# FLC100_shield_v2_0.net
KiCad netlist of a schematic drawn in EAGLE
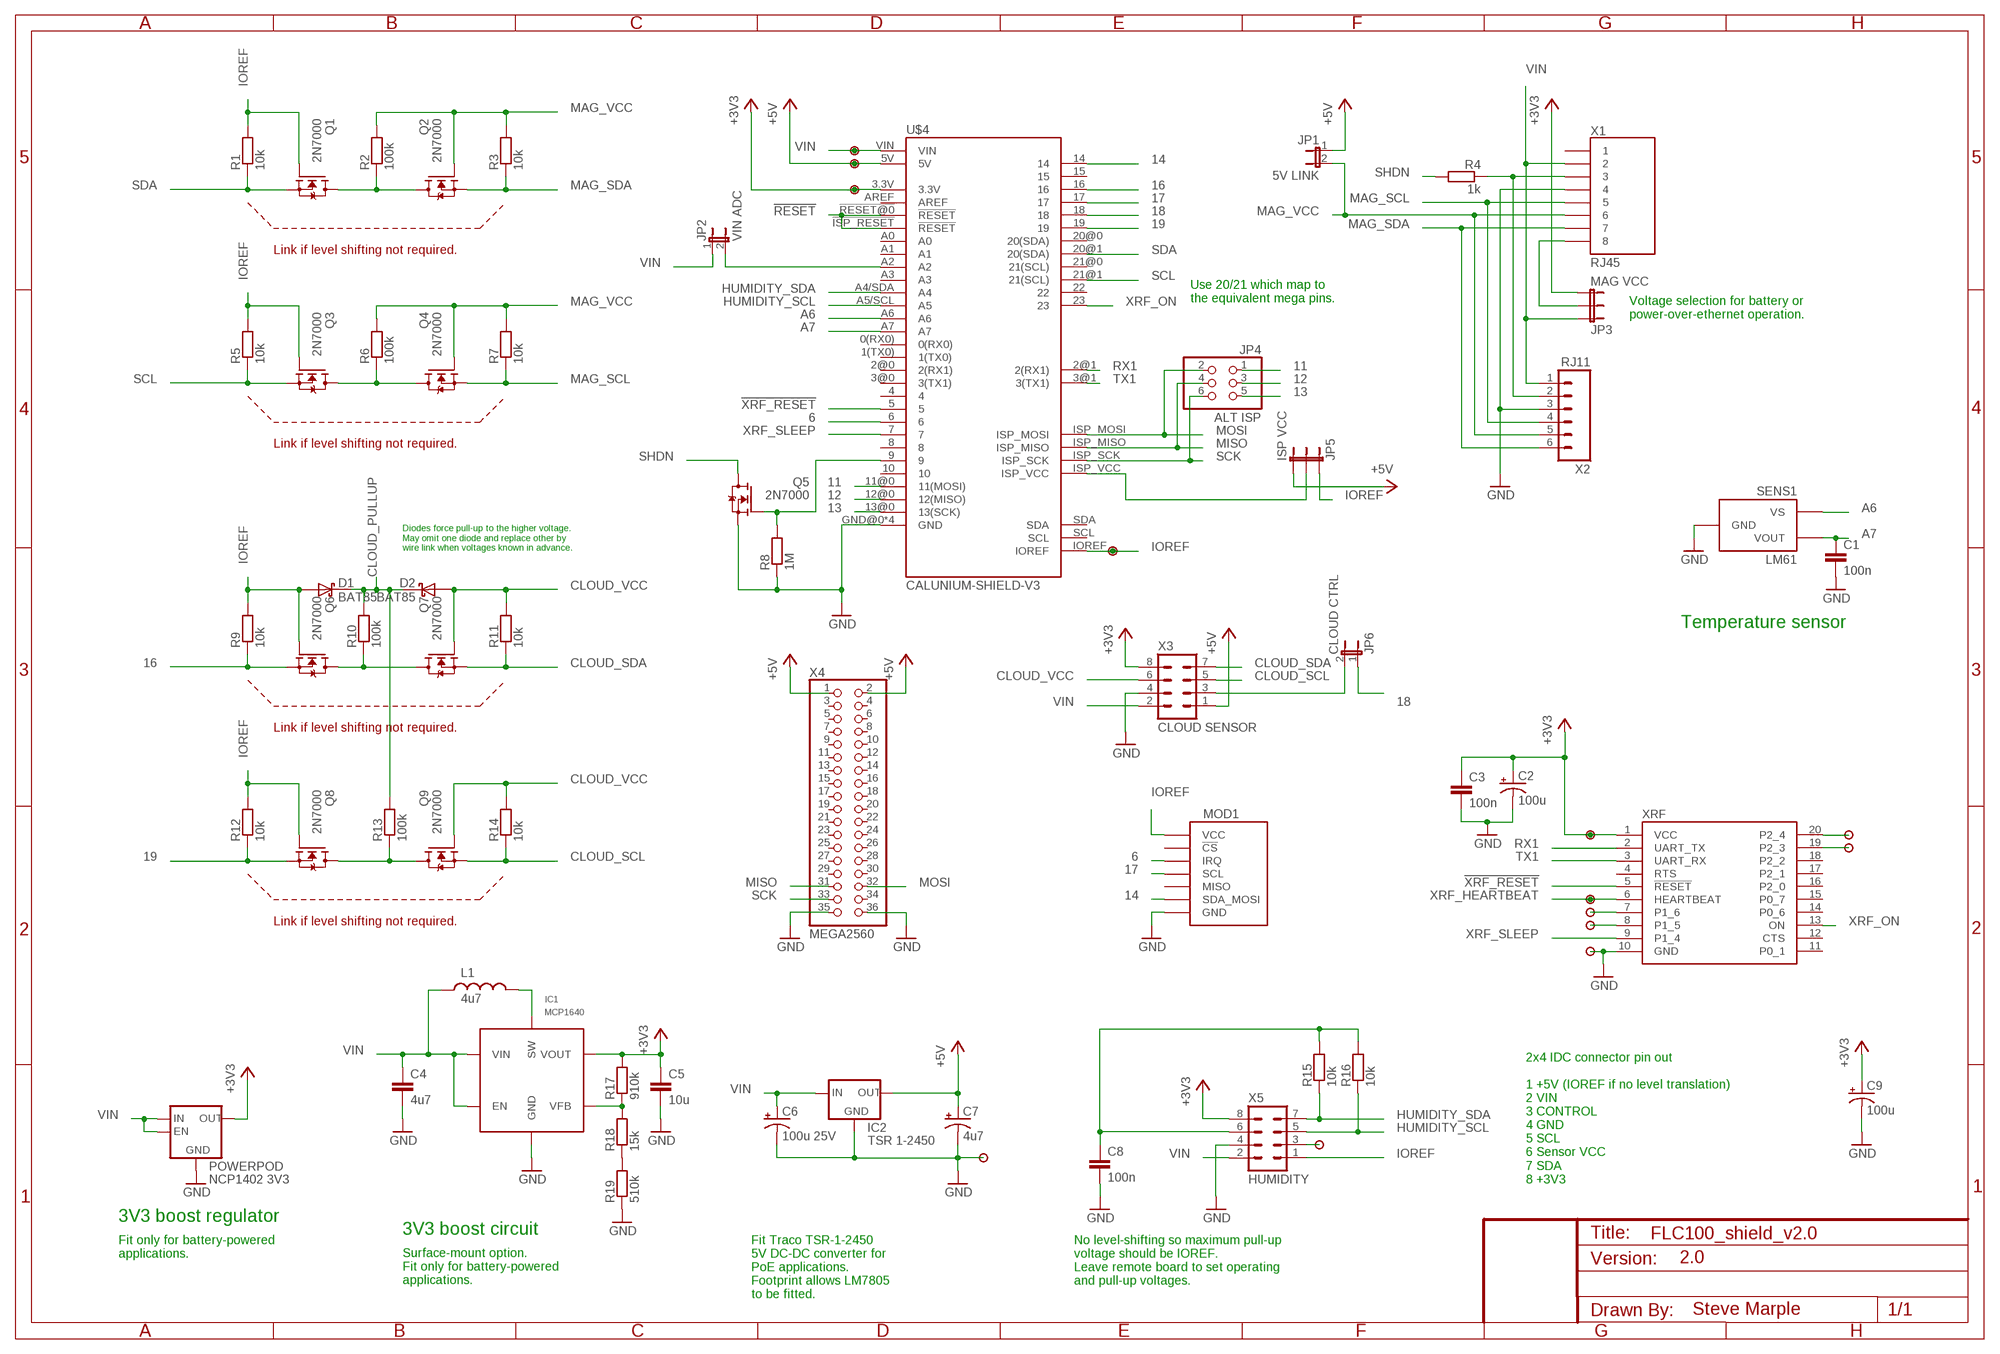
[diagram p0: schematic, sheet 1]

(export (version "E")
  (design (tool "Eeschema 10.0.6"))
  (components
    (comp (ref "C1")
      (value "100n")
      (footprint "eagle-import:CAP-PTH-SMALL")
      (libsource (lib "eagle-import") (part "CAPPTH"))
    )
    (comp (ref "C2")
      (value "100u")
      (footprint "eagle-import:CPOL-RADIAL-10UF-25V")
      (libsource (lib "eagle-import") (part "CAP_POLPTH2"))
    )
    (comp (ref "C3")
      (value "100n")
      (footprint "eagle-import:CAP-PTH-SMALL")
      (libsource (lib "eagle-import") (part "CAPPTH"))
    )
    (comp (ref "C4")
      (value "4u7")
      (footprint "eagle-import:1206-HAND")
      (libsource (lib "eagle-import") (part "C-EU1206-HAND"))
    )
    (comp (ref "C5")
      (value "10u")
      (footprint "eagle-import:1206-HAND")
      (libsource (lib "eagle-import") (part "C-EU1206-HAND"))
    )
    (comp (ref "C6")
      (value "100u 25V")
      (footprint "eagle-import:CPOL-RADIAL-100UF-25V-150MIL")
      (libsource (lib "eagle-import") (part "CAP_POL"))
    )
    (comp (ref "C7")
      (value "4u7")
      (footprint "eagle-import:CPOL-RADIAL-10UF-25V")
      (libsource (lib "eagle-import") (part "CAP_POLPTH2"))
    )
    (comp (ref "C8")
      (value "100n")
      (footprint "eagle-import:CAP-PTH-SMALL")
      (libsource (lib "eagle-import") (part "CAPPTH"))
    )
    (comp (ref "C9")
      (value "100u")
      (footprint "eagle-import:CPOL-RADIAL-10UF-25V")
      (libsource (lib "eagle-import") (part "CAP_POLPTH2"))
    )
    (comp (ref "D1")
      (value "BAT85")
      (footprint "eagle-import:DIODE-TH-0.4")
      (libsource (lib "eagle-import") (part "DIODE-SCHOTTKY"))
    )
    (comp (ref "D2")
      (value "BAT85")
      (footprint "eagle-import:DIODE-TH-0.4")
      (libsource (lib "eagle-import") (part "DIODE-SCHOTTKY"))
    )
    (comp (ref "IC1")
      (value "MCP1640")
      (footprint "eagle-import:SOT23-6-HAND")
      (libsource (lib "eagle-import") (part "MCP1640SOT23-6-HAND"))
    )
    (comp (ref "IC2")
      (value "TSR 1-2450")
      (footprint "eagle-import:78XXL")
      (libsource (lib "eagle-import") (part "V_REG_78XXSIDE"))
    )
    (comp (ref "JP1")
      (value "5V LINK")
      (footprint "eagle-import:1X02")
      (libsource (lib "eagle-import") (part "JUMPER-2PTH"))
    )
    (comp (ref "JP2")
      (value "VIN ADC")
      (footprint "eagle-import:1X02")
      (libsource (lib "eagle-import") (part "JUMPER-2PTH"))
    )
    (comp (ref "JP3")
      (value "MAG VCC")
      (footprint "eagle-import:1X03")
      (libsource (lib "eagle-import") (part "JUMPER-3PTH"))
    )
    (comp (ref "JP4")
      (value "ALT ISP")
      (footprint "eagle-import:2X03")
      (libsource (lib "eagle-import") (part "PINHD-2X3"))
    )
    (comp (ref "JP5")
      (value "ISP VCC")
      (footprint "eagle-import:1X03")
      (libsource (lib "eagle-import") (part "JUMPER-3PTH"))
    )
    (comp (ref "JP6")
      (value "CLOUD CTRL")
      (footprint "eagle-import:1X02")
      (libsource (lib "eagle-import") (part "JUMPER-2PTH"))
    )
    (comp (ref "L1")
      (value "4u7")
      (footprint "eagle-import:INDUCTOR-TH-2MM")
      (libsource (lib "eagle-import") (part "INDUCTORTH-2MM"))
    )
    (comp (ref "MOD1")
      (value "EMBEDDED_ADVENTURES_MOD-1016NO-HOLES")
      (footprint "eagle-import:EMBEDDED_ADVENTURES_MOD-1016-NO-HOLES")
      (libsource (lib "eagle-import") (part "EMBEDDED_ADVENTURES_MOD-1016NO-HOLES"))
    )
    (comp (ref "POWERPOD")
      (value "NCP1402 3V3")
      (footprint "eagle-import:CISECO_POWERPOD_NCP1402")
      (libsource (lib "eagle-import") (part "CISECO_POWERPOD_NCP1402"))
    )
    (comp (ref "Q1")
      (value "2N7000")
      (footprint "eagle-import:TO-92")
      (libsource (lib "eagle-import") (part "2N7000"))
    )
    (comp (ref "Q2")
      (value "2N7000")
      (footprint "eagle-import:TO-92")
      (libsource (lib "eagle-import") (part "2N7000"))
    )
    (comp (ref "Q3")
      (value "2N7000")
      (footprint "eagle-import:TO-92")
      (libsource (lib "eagle-import") (part "2N7000"))
    )
    (comp (ref "Q4")
      (value "2N7000")
      (footprint "eagle-import:TO-92")
      (libsource (lib "eagle-import") (part "2N7000"))
    )
    (comp (ref "Q5")
      (value "2N7000")
      (footprint "eagle-import:TO-92")
      (libsource (lib "eagle-import") (part "2N7000"))
    )
    (comp (ref "Q6")
      (value "2N7000")
      (footprint "eagle-import:TO-92")
      (libsource (lib "eagle-import") (part "2N7000"))
    )
    (comp (ref "Q7")
      (value "2N7000")
      (footprint "eagle-import:TO-92")
      (libsource (lib "eagle-import") (part "2N7000"))
    )
    (comp (ref "Q8")
      (value "2N7000")
      (footprint "eagle-import:TO-92")
      (libsource (lib "eagle-import") (part "2N7000"))
    )
    (comp (ref "Q9")
      (value "2N7000")
      (footprint "eagle-import:TO-92")
      (libsource (lib "eagle-import") (part "2N7000"))
    )
    (comp (ref "R1")
      (value "10k")
      (footprint "eagle-import:RES-AXIAL-0.4")
      (libsource (lib "eagle-import") (part "RESISTOR"))
    )
    (comp (ref "R2")
      (value "100k")
      (footprint "eagle-import:RES-AXIAL-0.4")
      (libsource (lib "eagle-import") (part "RESISTOR"))
    )
    (comp (ref "R3")
      (value "10k")
      (footprint "eagle-import:RES-AXIAL-0.4")
      (libsource (lib "eagle-import") (part "RESISTOR"))
    )
    (comp (ref "R4")
      (value "1k")
      (footprint "eagle-import:RES-AXIAL-0.4")
      (libsource (lib "eagle-import") (part "RESISTOR"))
    )
    (comp (ref "R5")
      (value "10k")
      (footprint "eagle-import:RES-AXIAL-0.4")
      (libsource (lib "eagle-import") (part "RESISTOR"))
    )
    (comp (ref "R6")
      (value "100k")
      (footprint "eagle-import:RES-AXIAL-0.4")
      (libsource (lib "eagle-import") (part "RESISTOR"))
    )
    (comp (ref "R7")
      (value "10k")
      (footprint "eagle-import:RES-AXIAL-0.4")
      (libsource (lib "eagle-import") (part "RESISTOR"))
    )
    (comp (ref "R8")
      (value "1M")
      (footprint "eagle-import:RES-AXIAL-0.4")
      (libsource (lib "eagle-import") (part "RESISTOR"))
    )
    (comp (ref "R9")
      (value "10k")
      (footprint "eagle-import:RES-AXIAL-0.4")
      (libsource (lib "eagle-import") (part "RESISTOR"))
    )
    (comp (ref "R10")
      (value "100k")
      (footprint "eagle-import:RES-AXIAL-0.4")
      (libsource (lib "eagle-import") (part "RESISTOR"))
    )
    (comp (ref "R11")
      (value "10k")
      (footprint "eagle-import:RES-AXIAL-0.4")
      (libsource (lib "eagle-import") (part "RESISTOR"))
    )
    (comp (ref "R12")
      (value "10k")
      (footprint "eagle-import:RES-AXIAL-0.4")
      (libsource (lib "eagle-import") (part "RESISTOR"))
    )
    (comp (ref "R13")
      (value "100k")
      (footprint "eagle-import:RES-AXIAL-0.4")
      (libsource (lib "eagle-import") (part "RESISTOR"))
    )
    (comp (ref "R14")
      (value "10k")
      (footprint "eagle-import:RES-AXIAL-0.4")
      (libsource (lib "eagle-import") (part "RESISTOR"))
    )
    (comp (ref "R15")
      (value "10k")
      (footprint "eagle-import:RES-AXIAL-0.4")
      (libsource (lib "eagle-import") (part "RESISTOR"))
    )
    (comp (ref "R16")
      (value "10k")
      (footprint "eagle-import:RES-AXIAL-0.4")
      (libsource (lib "eagle-import") (part "RESISTOR"))
    )
    (comp (ref "R17")
      (value "910k")
      (footprint "eagle-import:1206-HAND")
      (libsource (lib "eagle-import") (part "RESISTOR1206-HAND"))
    )
    (comp (ref "R18")
      (value "15k")
      (footprint "eagle-import:1206-HAND")
      (libsource (lib "eagle-import") (part "RESISTOR1206-HAND"))
    )
    (comp (ref "R19")
      (value "510k")
      (footprint "eagle-import:1206-HAND")
      (libsource (lib "eagle-import") (part "RESISTOR1206-HAND"))
    )
    (comp (ref "SENS1")
      (value "LM61")
      (footprint "eagle-import:TO-92")
      (libsource (lib "eagle-import") (part "LM61"))
    )
    (comp (ref "U$1")
      (value "PAD")
      (footprint "eagle-import:PAD")
      (libsource (lib "eagle-import") (part "PAD"))
    )
    (comp (ref "U$2")
      (value "PAD")
      (footprint "eagle-import:PAD")
      (libsource (lib "eagle-import") (part "PAD"))
    )
    (comp (ref "U$3")
      (value "PAD")
      (footprint "eagle-import:PAD")
      (libsource (lib "eagle-import") (part "PAD"))
    )
    (comp (ref "U$4")
      (value "CALUNIUM-SHIELD-V3")
      (footprint "eagle-import:CALUNIUM-SHIELD-NO-OUTLINE-NO-HOLES-NO-TEXT-V3")
      (libsource (lib "eagle-import") (part "CALUNIUM-SHIELD-V3V3-NO-HOLES-NO-TEXT"))
    )
    (comp (ref "U$5")
      (value "PAD")
      (footprint "eagle-import:PAD")
      (libsource (lib "eagle-import") (part "PAD"))
    )
    (comp (ref "U$6")
      (value "PAD")
      (footprint "eagle-import:PAD")
      (libsource (lib "eagle-import") (part "PAD"))
    )
    (comp (ref "U$7")
      (value "PAD")
      (footprint "eagle-import:PAD")
      (libsource (lib "eagle-import") (part "PAD"))
    )
    (comp (ref "U$8")
      (value "PAD")
      (footprint "eagle-import:PAD")
      (libsource (lib "eagle-import") (part "PAD"))
    )
    (comp (ref "U$9")
      (value "PAD")
      (footprint "eagle-import:PAD")
      (libsource (lib "eagle-import") (part "PAD"))
    )
    (comp (ref "U$10")
      (value "PAD")
      (footprint "eagle-import:PAD")
      (libsource (lib "eagle-import") (part "PAD"))
    )
    (comp (ref "U$11")
      (value "PAD")
      (footprint "eagle-import:PAD")
      (libsource (lib "eagle-import") (part "PAD"))
    )
    (comp (ref "U$12")
      (value "PAD")
      (footprint "eagle-import:PAD")
      (libsource (lib "eagle-import") (part "PAD"))
    )
    (comp (ref "U$13")
      (value "PAD")
      (footprint "eagle-import:PAD")
      (libsource (lib "eagle-import") (part "PAD"))
    )
    (comp (ref "U$14")
      (value "PAD")
      (footprint "eagle-import:PAD")
      (libsource (lib "eagle-import") (part "PAD"))
    )
    (comp (ref "X1")
      (value "RJ45")
      (footprint "eagle-import:RJ45-8")
      (libsource (lib "eagle-import") (part "RJ45-8PTH"))
    )
    (comp (ref "X2")
      (value "RJ11")
      (footprint "eagle-import:RJ11-6")
      (libsource (lib "eagle-import") (part "RJ11-6PTH"))
    )
    (comp (ref "X3")
      (value "CLOUD SENSOR")
      (footprint "eagle-import:ML8")
      (libsource (lib "eagle-import") (part "ML8"))
    )
    (comp (ref "X4")
      (value "MEGA2560")
      (footprint "eagle-import:2X18")
      (libsource (lib "eagle-import") (part "PINHD-2X18"))
    )
    (comp (ref "X5")
      (value "HUMIDITY")
      (footprint "eagle-import:ML8")
      (libsource (lib "eagle-import") (part "ML8"))
    )
    (comp (ref "XRF")
      (value "XRFB1")
      (footprint "eagle-import:XBEE")
      (libsource (lib "eagle-import") (part "XRFB1"))
    )
  )
  (nets
    (net (code "1") (name "+3V3") (class "Default")
      (node (ref "C2") (pin "1") (pinfunction "+_1") (pintype "passive"))
      (node (ref "C3") (pin "1") (pinfunction "1_1") (pintype "passive"))
      (node (ref "C5") (pin "1") (pinfunction "1_1") (pintype "passive"))
      (node (ref "C9") (pin "1") (pinfunction "+_1") (pintype "passive"))
      (node (ref "IC1") (pin "5") (pinfunction "VOUT_5") (pintype "power_in"))
      (node (ref "JP3") (pin "3") (pinfunction "3_3") (pintype "passive"))
      (node (ref "POWERPOD") (pin "VOUT") (pinfunction "OUT_VOUT") (pintype "power_in"))
      (node (ref "R17") (pin "2") (pinfunction "2_2") (pintype "passive"))
      (node (ref "U$3") (pin "1") (pinfunction "1_1") (pintype "bidirectional"))
      (node (ref "U$4") (pin "3.3V") (pinfunction "3.3V_3.3V") (pintype "bidirectional"))
      (node (ref "U$6") (pin "1") (pinfunction "1_1") (pintype "bidirectional"))
      (node (ref "X3") (pin "8") (pinfunction "8_8") (pintype "passive"))
      (node (ref "X5") (pin "8") (pinfunction "8_8") (pintype "passive"))
      (node (ref "XRF") (pin "1") (pinfunction "VCC_1") (pintype "power_in"))
    )
    (net (code "2") (name "+5V") (class "Default")
      (node (ref "C7") (pin "1") (pinfunction "+_1") (pintype "passive"))
      (node (ref "IC2") (pin "OUT") (pinfunction "OUT_OUT") (pintype "power_in"))
      (node (ref "JP1") (pin "1") (pinfunction "1_1") (pintype "passive"))
      (node (ref "JP5") (pin "3") (pinfunction "3_3") (pintype "passive"))
      (node (ref "U$2") (pin "1") (pinfunction "1_1") (pintype "bidirectional"))
      (node (ref "U$4") (pin "5V") (pinfunction "5V_5V") (pintype "bidirectional"))
      (node (ref "X3") (pin "1") (pinfunction "1_1") (pintype "passive"))
      (node (ref "X4") (pin "1") (pinfunction "1_1") (pintype "passive"))
      (node (ref "X4") (pin "2") (pinfunction "2_2") (pintype "passive"))
    )
    (net (code "3") (name "/6") (class "Default")
      (node (ref "MOD1") (pin "IRQ") (pinfunction "IRQ_IRQ") (pintype "bidirectional"))
      (node (ref "U$4") (pin "6") (pinfunction "6_6") (pintype "bidirectional"))
    )
    (net (code "4") (name "/11") (class "Default")
      (node (ref "JP4") (pin "1") (pinfunction "1_1") (pintype "passive"))
      (node (ref "U$4") (pin "11@0") (pinfunction "11(MOSI)_11@0") (pintype "bidirectional"))
    )
    (net (code "5") (name "/12") (class "Default")
      (node (ref "JP4") (pin "3") (pinfunction "3_3") (pintype "passive"))
      (node (ref "U$4") (pin "12@0") (pinfunction "12(MISO)_12@0") (pintype "bidirectional"))
    )
    (net (code "6") (name "/13") (class "Default")
      (node (ref "JP4") (pin "5") (pinfunction "5_5") (pintype "passive"))
      (node (ref "U$4") (pin "13@0") (pinfunction "13(SCK)_13@0") (pintype "bidirectional"))
    )
    (net (code "7") (name "/14") (class "Default")
      (node (ref "MOD1") (pin "SDA_MOSI") (pinfunction "SDA_MOSI_SDA_MOSI") (pintype "bidirectional"))
      (node (ref "U$4") (pin "14") (pinfunction "14_14") (pintype "bidirectional"))
    )
    (net (code "8") (name "/16") (class "Default")
      (node (ref "Q6") (pin "1") (pinfunction "S_1") (pintype "passive"))
      (node (ref "R9") (pin "P$1") (pinfunction "1_P$1") (pintype "passive"))
      (node (ref "U$4") (pin "16") (pinfunction "16_16") (pintype "bidirectional"))
    )
    (net (code "9") (name "/17") (class "Default")
      (node (ref "MOD1") (pin "SCL") (pinfunction "SCL_SCL") (pintype "bidirectional"))
      (node (ref "U$4") (pin "17") (pinfunction "17_17") (pintype "bidirectional"))
    )
    (net (code "10") (name "/18") (class "Default")
      (node (ref "JP6") (pin "1") (pinfunction "1_1") (pintype "passive"))
      (node (ref "U$4") (pin "18") (pinfunction "18_18") (pintype "bidirectional"))
    )
    (net (code "11") (name "/19") (class "Default")
      (node (ref "Q8") (pin "1") (pinfunction "S_1") (pintype "passive"))
      (node (ref "R12") (pin "P$1") (pinfunction "1_P$1") (pintype "passive"))
      (node (ref "U$4") (pin "19") (pinfunction "19_19") (pintype "bidirectional"))
    )
    (net (code "12") (name "/A6") (class "Default")
      (node (ref "SENS1") (pin "1") (pinfunction "VS_1") (pintype "bidirectional"))
      (node (ref "U$4") (pin "A6") (pinfunction "A6_A6") (pintype "bidirectional"))
    )
    (net (code "13") (name "/A7") (class "Default")
      (node (ref "C1") (pin "1") (pinfunction "1_1") (pintype "passive"))
      (node (ref "SENS1") (pin "2") (pinfunction "VOUT_2") (pintype "bidirectional"))
      (node (ref "U$4") (pin "A7") (pinfunction "A7_A7") (pintype "bidirectional"))
    )
    (net (code "14") (name "/CLOUD_PULLUP") (class "Default")
      (node (ref "D1") (pin "C") (pinfunction "C_C") (pintype "passive"))
      (node (ref "D2") (pin "C") (pinfunction "C_C") (pintype "passive"))
      (node (ref "R10") (pin "P$2") (pinfunction "2_P$2") (pintype "passive"))
      (node (ref "R13") (pin "P$2") (pinfunction "2_P$2") (pintype "passive"))
    )
    (net (code "15") (name "/CLOUD_SCL") (class "Default")
      (node (ref "Q9") (pin "1") (pinfunction "S_1") (pintype "passive"))
      (node (ref "R14") (pin "P$1") (pinfunction "1_P$1") (pintype "passive"))
      (node (ref "X3") (pin "5") (pinfunction "5_5") (pintype "passive"))
    )
    (net (code "16") (name "/CLOUD_SDA") (class "Default")
      (node (ref "Q7") (pin "1") (pinfunction "S_1") (pintype "passive"))
      (node (ref "R11") (pin "P$1") (pinfunction "1_P$1") (pintype "passive"))
      (node (ref "X3") (pin "7") (pinfunction "7_7") (pintype "passive"))
    )
    (net (code "17") (name "/CLOUD_VCC") (class "Default")
      (node (ref "D2") (pin "A") (pinfunction "A_A") (pintype "passive"))
      (node (ref "Q7") (pin "2") (pinfunction "G_2") (pintype "passive"))
      (node (ref "Q9") (pin "2") (pinfunction "G_2") (pintype "passive"))
      (node (ref "R11") (pin "P$2") (pinfunction "2_P$2") (pintype "passive"))
      (node (ref "R14") (pin "P$2") (pinfunction "2_P$2") (pintype "passive"))
      (node (ref "X3") (pin "6") (pinfunction "6_6") (pintype "passive"))
    )
    (net (code "18") (name "/HUMIDITY_SCL") (class "Default")
      (node (ref "R16") (pin "P$1") (pinfunction "1_P$1") (pintype "passive"))
      (node (ref "U$4") (pin "A5/SCL") (pinfunction "A5_A5/SCL") (pintype "bidirectional"))
      (node (ref "X5") (pin "5") (pinfunction "5_5") (pintype "passive"))
    )
    (net (code "19") (name "/HUMIDITY_SDA") (class "Default")
      (node (ref "R15") (pin "P$1") (pinfunction "1_P$1") (pintype "passive"))
      (node (ref "U$4") (pin "A4/SDA") (pinfunction "A4_A4/SDA") (pintype "bidirectional"))
      (node (ref "X5") (pin "7") (pinfunction "7_7") (pintype "passive"))
    )
    (net (code "20") (name "/IOREF") (class "Default")
      (node (ref "D1") (pin "A") (pinfunction "A_A") (pintype "passive"))
      (node (ref "JP5") (pin "1") (pinfunction "1_1") (pintype "passive"))
      (node (ref "MOD1") (pin "VCC") (pinfunction "VCC_VCC") (pintype "power_in"))
      (node (ref "Q1") (pin "2") (pinfunction "G_2") (pintype "passive"))
      (node (ref "Q3") (pin "2") (pinfunction "G_2") (pintype "passive"))
      (node (ref "Q6") (pin "2") (pinfunction "G_2") (pintype "passive"))
      (node (ref "Q8") (pin "2") (pinfunction "G_2") (pintype "passive"))
      (node (ref "R1") (pin "P$2") (pinfunction "2_P$2") (pintype "passive"))
      (node (ref "R12") (pin "P$2") (pinfunction "2_P$2") (pintype "passive"))
      (node (ref "R5") (pin "P$2") (pinfunction "2_P$2") (pintype "passive"))
      (node (ref "R9") (pin "P$2") (pinfunction "2_P$2") (pintype "passive"))
      (node (ref "U$4") (pin "IOREF") (pinfunction "IOREF_IOREF") (pintype "bidirectional"))
      (node (ref "U$5") (pin "1") (pinfunction "1_1") (pintype "bidirectional"))
      (node (ref "X5") (pin "1") (pinfunction "1_1") (pintype "passive"))
    )
    (net (code "21") (name "/MAG_SCL") (class "Default")
      (node (ref "Q4") (pin "1") (pinfunction "S_1") (pintype "passive"))
      (node (ref "R7") (pin "P$1") (pinfunction "1_P$1") (pintype "passive"))
      (node (ref "X1") (pin "5") (pinfunction "5_5") (pintype "bidirectional"))
      (node (ref "X2") (pin "4") (pinfunction "4_4") (pintype "passive"))
    )
    (net (code "22") (name "/MAG_SDA") (class "Default")
      (node (ref "Q2") (pin "1") (pinfunction "S_1") (pintype "passive"))
      (node (ref "R3") (pin "P$1") (pinfunction "1_P$1") (pintype "passive"))
      (node (ref "X1") (pin "7") (pinfunction "7_7") (pintype "bidirectional"))
      (node (ref "X2") (pin "6") (pinfunction "6_6") (pintype "passive"))
    )
    (net (code "23") (name "/MAG_VCC") (class "Default")
      (node (ref "JP1") (pin "2") (pinfunction "2_2") (pintype "passive"))
      (node (ref "Q2") (pin "2") (pinfunction "G_2") (pintype "passive"))
      (node (ref "Q4") (pin "2") (pinfunction "G_2") (pintype "passive"))
      (node (ref "R2") (pin "P$2") (pinfunction "2_P$2") (pintype "passive"))
      (node (ref "R3") (pin "P$2") (pinfunction "2_P$2") (pintype "passive"))
      (node (ref "R6") (pin "P$2") (pinfunction "2_P$2") (pintype "passive"))
      (node (ref "R7") (pin "P$2") (pinfunction "2_P$2") (pintype "passive"))
      (node (ref "X1") (pin "6") (pinfunction "6_6") (pintype "bidirectional"))
      (node (ref "X2") (pin "5") (pinfunction "5_5") (pintype "passive"))
    )
    (net (code "24") (name "/MISO") (class "Default")
      (node (ref "JP4") (pin "4") (pinfunction "4_4") (pintype "passive"))
      (node (ref "U$4") (pin "ISP_MISO") (pinfunction "ISP_MISO_ISP_MISO") (pintype "bidirectional"))
      (node (ref "X4") (pin "31") (pinfunction "31_31") (pintype "passive"))
    )
    (net (code "25") (name "/MOSI") (class "Default")
      (node (ref "JP4") (pin "2") (pinfunction "2_2") (pintype "passive"))
      (node (ref "U$4") (pin "ISP_MOSI") (pinfunction "ISP_MOSI_ISP_MOSI") (pintype "bidirectional"))
      (node (ref "X4") (pin "32") (pinfunction "32_32") (pintype "passive"))
    )
    (net (code "26") (name "/RX1") (class "Default")
      (node (ref "U$4") (pin "2@1") (pinfunction "2(RX1)_2@1") (pintype "bidirectional"))
      (node (ref "XRF") (pin "2") (pinfunction "UART_TX_2") (pintype "output"))
    )
    (net (code "27") (name "/SCK") (class "Default")
      (node (ref "JP4") (pin "6") (pinfunction "6_6") (pintype "passive"))
      (node (ref "U$4") (pin "ISP_SCK") (pinfunction "ISP_SCK_ISP_SCK") (pintype "bidirectional"))
      (node (ref "X4") (pin "33") (pinfunction "33_33") (pintype "passive"))
    )
    (net (code "28") (name "/SCL") (class "Default")
      (node (ref "Q3") (pin "1") (pinfunction "S_1") (pintype "passive"))
      (node (ref "R5") (pin "P$1") (pinfunction "1_P$1") (pintype "passive"))
      (node (ref "U$4") (pin "21@1") (pinfunction "21(SCL)_21@1") (pintype "bidirectional"))
    )
    (net (code "29") (name "/SDA") (class "Default")
      (node (ref "Q1") (pin "1") (pinfunction "S_1") (pintype "passive"))
      (node (ref "R1") (pin "P$1") (pinfunction "1_P$1") (pintype "passive"))
      (node (ref "U$4") (pin "20@1") (pinfunction "20(SDA)_20@1") (pintype "bidirectional"))
    )
    (net (code "30") (name "/SHDN") (class "Default")
      (node (ref "Q5") (pin "3") (pinfunction "D_3") (pintype "passive"))
      (node (ref "R4") (pin "P$2") (pinfunction "2_P$2") (pintype "passive"))
    )
    (net (code "31") (name "/TX1") (class "Default")
      (node (ref "U$4") (pin "3@1") (pinfunction "3(TX1)_3@1") (pintype "bidirectional"))
      (node (ref "XRF") (pin "3") (pinfunction "UART_RX_3") (pintype "input"))
    )
    (net (code "32") (name "/VIN") (class "Default")
      (node (ref "C4") (pin "1") (pinfunction "1_1") (pintype "passive"))
      (node (ref "C6") (pin "1") (pinfunction "+_1") (pintype "passive"))
      (node (ref "IC1") (pin "3") (pinfunction "EN_3") (pintype "input"))
      (node (ref "IC1") (pin "6") (pinfunction "VIN_6") (pintype "input"))
      (node (ref "IC2") (pin "IN") (pinfunction "IN_IN") (pintype "input"))
      (node (ref "JP2") (pin "1") (pinfunction "1_1") (pintype "passive"))
      (node (ref "JP3") (pin "1") (pinfunction "1_1") (pintype "passive"))
      (node (ref "L1") (pin "P$1") (pinfunction "1_P$1") (pintype "passive"))
      (node (ref "POWERPOD") (pin "ENABLE") (pinfunction "ENABLE_ENABLE") (pintype "input"))
      (node (ref "POWERPOD") (pin "VIN") (pinfunction "IN_VIN") (pintype "input"))
      (node (ref "U$1") (pin "1") (pinfunction "1_1") (pintype "bidirectional"))
      (node (ref "U$4") (pin "VIN") (pinfunction "VIN_VIN") (pintype "bidirectional"))
      (node (ref "X1") (pin "2") (pinfunction "2_2") (pintype "bidirectional"))
      (node (ref "X2") (pin "1") (pinfunction "1_1") (pintype "passive"))
      (node (ref "X3") (pin "2") (pinfunction "2_2") (pintype "passive"))
      (node (ref "X5") (pin "2") (pinfunction "2_2") (pintype "passive"))
    )
    (net (code "33") (name "/XRF_HEARTBEAT") (class "Default")
      (node (ref "U$9") (pin "1") (pinfunction "1_1") (pintype "bidirectional"))
      (node (ref "XRF") (pin "6") (pinfunction "HEARTBEAT_6") (pintype "bidirectional"))
    )
    (net (code "34") (name "/XRF_ON") (class "Default")
      (node (ref "U$4") (pin "23") (pinfunction "23_23") (pintype "bidirectional"))
      (node (ref "XRF") (pin "13") (pinfunction "ON_13") (pintype "bidirectional"))
    )
    (net (code "35") (name "/XRF_SLEEP") (class "Default")
      (node (ref "U$4") (pin "7") (pinfunction "7_7") (pintype "bidirectional"))
      (node (ref "XRF") (pin "9") (pinfunction "P1_4_9") (pintype "bidirectional"))
    )
    (net (code "36") (name "/~{RESET}") (class "Default")
      (node (ref "U$4") (pin "!ISP_RESET") (pinfunction "~{RESET}_!ISP_RESET") (pintype "bidirectional"))
      (node (ref "U$4") (pin "!RESET@0") (pinfunction "~{RESET}_!RESET@0") (pintype "bidirectional"))
    )
    (net (code "37") (name "/~{XRF_RESET}") (class "Default")
      (node (ref "U$4") (pin "5") (pinfunction "5_5") (pintype "bidirectional"))
      (node (ref "XRF") (pin "5") (pinfunction "~{RESET}_5") (pintype "input"))
    )
    (net (code "38") (name "GND") (class "Default")
      (node (ref "C1") (pin "2") (pinfunction "2_2") (pintype "passive"))
      (node (ref "C2") (pin "2") (pinfunction "-_2") (pintype "passive"))
      (node (ref "C3") (pin "2") (pinfunction "2_2") (pintype "passive"))
      (node (ref "C4") (pin "2") (pinfunction "2_2") (pintype "passive"))
      (node (ref "C5") (pin "2") (pinfunction "2_2") (pintype "passive"))
      (node (ref "C6") (pin "2") (pinfunction "-_2") (pintype "passive"))
      (node (ref "C7") (pin "2") (pinfunction "-_2") (pintype "passive"))
      (node (ref "C8") (pin "2") (pinfunction "2_2") (pintype "passive"))
      (node (ref "C9") (pin "2") (pinfunction "-_2") (pintype "passive"))
      (node (ref "IC1") (pin "2") (pinfunction "GND_2") (pintype "power_in"))
      (node (ref "IC2") (pin "GND") (pinfunction "GND_GND") (pintype "power_in"))
      (node (ref "MOD1") (pin "GND") (pinfunction "GND_GND") (pintype "power_in"))
      (node (ref "POWERPOD") (pin "GND") (pinfunction "GND_GND") (pintype "power_in"))
      (node (ref "Q5") (pin "1") (pinfunction "S_1") (pintype "passive"))
      (node (ref "R19") (pin "1") (pinfunction "1_1") (pintype "passive"))
      (node (ref "R8") (pin "P$1") (pinfunction "1_P$1") (pintype "passive"))
      (node (ref "SENS1") (pin "3") (pinfunction "GND_3") (pintype "bidirectional"))
      (node (ref "U$12") (pin "1") (pinfunction "1_1") (pintype "bidirectional"))
      (node (ref "U$14") (pin "1") (pinfunction "1_1") (pintype "bidirectional"))
      (node (ref "U$4") (pin "GND@0") (pinfunction "GND_GND@0") (pintype "bidirectional"))
      (node (ref "U$4") (pin "GND@1") (pinfunction "GND_GND@1") (pintype "bidirectional"))
      (node (ref "U$4") (pin "GND@2") (pinfunction "GND_GND@2") (pintype "bidirectional"))
      (node (ref "U$4") (pin "GND@3") (pinfunction "GND_GND@3") (pintype "bidirectional"))
      (node (ref "X1") (pin "4") (pinfunction "4_4") (pintype "bidirectional"))
      (node (ref "X2") (pin "3") (pinfunction "3_3") (pintype "passive"))
      (node (ref "X3") (pin "4") (pinfunction "4_4") (pintype "passive"))
      (node (ref "X4") (pin "35") (pinfunction "35_35") (pintype "passive"))
      (node (ref "X4") (pin "36") (pinfunction "36_36") (pintype "passive"))
      (node (ref "X5") (pin "4") (pinfunction "4_4") (pintype "passive"))
      (node (ref "XRF") (pin "10") (pinfunction "GND_10") (pintype "power_in"))
    )
    (net (code "39") (name "Net-(IC1-SW)") (class "Default")
      (node (ref "IC1") (pin "1") (pinfunction "SW_1") (pintype "passive"))
      (node (ref "L1") (pin "P$2") (pinfunction "2_P$2") (pintype "passive"))
    )
    (net (code "40") (name "Net-(IC1-VFB)") (class "Default")
      (node (ref "IC1") (pin "4") (pinfunction "VFB_4") (pintype "input"))
      (node (ref "R17") (pin "1") (pinfunction "1_1") (pintype "passive"))
      (node (ref "R18") (pin "2") (pinfunction "2_2") (pintype "passive"))
    )
    (net (code "41") (name "Net-(JP2-Pad2)") (class "Default")
      (node (ref "JP2") (pin "2") (pinfunction "2_2") (pintype "passive"))
      (node (ref "U$4") (pin "A2") (pinfunction "A2_A2") (pintype "bidirectional"))
    )
    (net (code "42") (name "Net-(JP3-Pad2)") (class "Default")
      (node (ref "JP3") (pin "2") (pinfunction "2_2") (pintype "passive"))
      (node (ref "X1") (pin "8") (pinfunction "8_8") (pintype "bidirectional"))
    )
    (net (code "43") (name "Net-(JP5-Pad2)") (class "Default")
      (node (ref "JP5") (pin "2") (pinfunction "2_2") (pintype "passive"))
      (node (ref "U$4") (pin "ISP_VCC") (pinfunction "ISP_VCC_ISP_VCC") (pintype "bidirectional"))
    )
    (net (code "44") (name "Net-(JP6-Pad2)") (class "Default")
      (node (ref "JP6") (pin "2") (pinfunction "2_2") (pintype "passive"))
      (node (ref "X3") (pin "3") (pinfunction "3_3") (pintype "passive"))
    )
    (net (code "45") (name "Net-(Q1-D)") (class "Default")
      (node (ref "Q1") (pin "3") (pinfunction "D_3") (pintype "passive"))
      (node (ref "Q2") (pin "3") (pinfunction "D_3") (pintype "passive"))
      (node (ref "R2") (pin "P$1") (pinfunction "1_P$1") (pintype "passive"))
    )
    (net (code "46") (name "Net-(Q3-D)") (class "Default")
      (node (ref "Q3") (pin "3") (pinfunction "D_3") (pintype "passive"))
      (node (ref "Q4") (pin "3") (pinfunction "D_3") (pintype "passive"))
      (node (ref "R6") (pin "P$1") (pinfunction "1_P$1") (pintype "passive"))
    )
    (net (code "47") (name "Net-(Q5-G)") (class "Default")
      (node (ref "Q5") (pin "2") (pinfunction "G_2") (pintype "passive"))
      (node (ref "R8") (pin "P$2") (pinfunction "2_P$2") (pintype "passive"))
      (node (ref "U$4") (pin "9") (pinfunction "9_9") (pintype "bidirectional"))
    )
    (net (code "48") (name "Net-(Q6-D)") (class "Default")
      (node (ref "Q6") (pin "3") (pinfunction "D_3") (pintype "passive"))
      (node (ref "Q7") (pin "3") (pinfunction "D_3") (pintype "passive"))
      (node (ref "R10") (pin "P$1") (pinfunction "1_P$1") (pintype "passive"))
    )
    (net (code "49") (name "Net-(Q8-D)") (class "Default")
      (node (ref "Q8") (pin "3") (pinfunction "D_3") (pintype "passive"))
      (node (ref "Q9") (pin "3") (pinfunction "D_3") (pintype "passive"))
      (node (ref "R13") (pin "P$1") (pinfunction "1_P$1") (pintype "passive"))
    )
    (net (code "50") (name "Net-(R4-1)") (class "Default")
      (node (ref "R4") (pin "P$1") (pinfunction "1_P$1") (pintype "passive"))
      (node (ref "X1") (pin "3") (pinfunction "3_3") (pintype "bidirectional"))
      (node (ref "X2") (pin "2") (pinfunction "2_2") (pintype "passive"))
    )
    (net (code "51") (name "Net-(R15-2)") (class "Default")
      (node (ref "C8") (pin "1") (pinfunction "1_1") (pintype "passive"))
      (node (ref "R15") (pin "P$2") (pinfunction "2_P$2") (pintype "passive"))
      (node (ref "R16") (pin "P$2") (pinfunction "2_P$2") (pintype "passive"))
      (node (ref "X5") (pin "6") (pinfunction "6_6") (pintype "passive"))
    )
    (net (code "52") (name "Net-(R18-Pad1)") (class "Default")
      (node (ref "R18") (pin "1") (pinfunction "1_1") (pintype "passive"))
      (node (ref "R19") (pin "2") (pinfunction "2_2") (pintype "passive"))
    )
    (net (code "53") (name "Net-(U$13-Pad1)") (class "Default")
      (node (ref "U$13") (pin "1") (pinfunction "1_1") (pintype "bidirectional"))
      (node (ref "X5") (pin "3") (pinfunction "3_3") (pintype "passive"))
    )
    (net (code "54") (name "Net-(XRF-P1_5)") (class "Default")
      (node (ref "U$11") (pin "1") (pinfunction "1_1") (pintype "bidirectional"))
      (node (ref "XRF") (pin "8") (pinfunction "P1_5_8") (pintype "bidirectional"))
    )
    (net (code "55") (name "Net-(XRF-P1_6)") (class "Default")
      (node (ref "U$10") (pin "1") (pinfunction "1_1") (pintype "bidirectional"))
      (node (ref "XRF") (pin "7") (pinfunction "P1_6_7") (pintype "bidirectional"))
    )
    (net (code "56") (name "Net-(XRF-P2_3)") (class "Default")
      (node (ref "U$8") (pin "1") (pinfunction "1_1") (pintype "bidirectional"))
      (node (ref "XRF") (pin "19") (pinfunction "P2_3_19") (pintype "bidirectional"))
    )
    (net (code "57") (name "Net-(XRF-P2_4)") (class "Default")
      (node (ref "U$7") (pin "1") (pinfunction "1_1") (pintype "bidirectional"))
      (node (ref "XRF") (pin "20") (pinfunction "P2_4_20") (pintype "input"))
    )
    (net (code "58") (name "unconnected-(MOD1-PadMISO)") (class "Default")
      (node (ref "MOD1") (pin "MISO") (pinfunction "MISO_MISO") (pintype "bidirectional"))
    )
    (net (code "59") (name "unconnected-(MOD1-~{CS}-Pad!CS)") (class "Default")
      (node (ref "MOD1") (pin "!CS") (pinfunction "~{CS}_!CS") (pintype "bidirectional"))
    )
    (net (code "60") (name "unconnected-(U$4-2(RX1)-Pad2@0)") (class "Default")
      (node (ref "U$4") (pin "2@0") (pinfunction "2(RX1)_2@0") (pintype "bidirectional"))
    )
    (net (code "61") (name "unconnected-(U$4-3(TX1)-Pad3@0)") (class "Default")
      (node (ref "U$4") (pin "3@0") (pinfunction "3(TX1)_3@0") (pintype "bidirectional"))
    )
    (net (code "62") (name "unconnected-(U$4-20(SDA)-Pad20@0)") (class "Default")
      (node (ref "U$4") (pin "20@0") (pinfunction "20(SDA)_20@0") (pintype "bidirectional"))
    )
    (net (code "63") (name "unconnected-(U$4-21(SCL)-Pad21@0)") (class "Default")
      (node (ref "U$4") (pin "21@0") (pinfunction "21(SCL)_21@0") (pintype "bidirectional"))
    )
    (net (code "64") (name "unconnected-(U$4-Pad0(RX0))") (class "Default")
      (node (ref "U$4") (pin "0(RX0)") (pinfunction "0(RX0)_0(RX0)") (pintype "bidirectional"))
    )
    (net (code "65") (name "unconnected-(U$4-Pad1(TX0))") (class "Default")
      (node (ref "U$4") (pin "1(TX0)") (pinfunction "1(TX0)_1(TX0)") (pintype "bidirectional"))
    )
    (net (code "66") (name "unconnected-(U$4-Pad4)") (class "Default")
      (node (ref "U$4") (pin "4") (pinfunction "4_4") (pintype "bidirectional"))
    )
    (net (code "67") (name "unconnected-(U$4-Pad8)") (class "Default")
      (node (ref "U$4") (pin "8") (pinfunction "8_8") (pintype "bidirectional"))
    )
    (net (code "68") (name "unconnected-(U$4-Pad10)") (class "Default")
      (node (ref "U$4") (pin "10") (pinfunction "10_10") (pintype "bidirectional"))
    )
    (net (code "69") (name "unconnected-(U$4-Pad15)") (class "Default")
      (node (ref "U$4") (pin "15") (pinfunction "15_15") (pintype "bidirectional"))
    )
    (net (code "70") (name "unconnected-(U$4-Pad22)") (class "Default")
      (node (ref "U$4") (pin "22") (pinfunction "22_22") (pintype "bidirectional"))
    )
    (net (code "71") (name "unconnected-(U$4-PadA0)") (class "Default")
      (node (ref "U$4") (pin "A0") (pinfunction "A0_A0") (pintype "bidirectional"))
    )
    (net (code "72") (name "unconnected-(U$4-PadA1)") (class "Default")
      (node (ref "U$4") (pin "A1") (pinfunction "A1_A1") (pintype "bidirectional"))
    )
    (net (code "73") (name "unconnected-(U$4-PadA3)") (class "Default")
      (node (ref "U$4") (pin "A3") (pinfunction "A3_A3") (pintype "bidirectional"))
    )
    (net (code "74") (name "unconnected-(U$4-PadAREF)") (class "Default")
      (node (ref "U$4") (pin "AREF") (pinfunction "AREF_AREF") (pintype "bidirectional"))
    )
    (net (code "75") (name "unconnected-(U$4-PadSCL)") (class "Default")
      (node (ref "U$4") (pin "SCL") (pinfunction "SCL_SCL") (pintype "bidirectional"))
    )
    (net (code "76") (name "unconnected-(U$4-PadSDA)") (class "Default")
      (node (ref "U$4") (pin "SDA") (pinfunction "SDA_SDA") (pintype "bidirectional"))
    )
    (net (code "77") (name "unconnected-(X1-Pad1)") (class "Default")
      (node (ref "X1") (pin "1") (pinfunction "1_1") (pintype "bidirectional"))
    )
    (net (code "78") (name "unconnected-(X4-Pad3)") (class "Default")
      (node (ref "X4") (pin "3") (pinfunction "3_3") (pintype "passive"))
    )
    (net (code "79") (name "unconnected-(X4-Pad4)") (class "Default")
      (node (ref "X4") (pin "4") (pinfunction "4_4") (pintype "passive"))
    )
    (net (code "80") (name "unconnected-(X4-Pad5)") (class "Default")
      (node (ref "X4") (pin "5") (pinfunction "5_5") (pintype "passive"))
    )
    (net (code "81") (name "unconnected-(X4-Pad6)") (class "Default")
      (node (ref "X4") (pin "6") (pinfunction "6_6") (pintype "passive"))
    )
    (net (code "82") (name "unconnected-(X4-Pad7)") (class "Default")
      (node (ref "X4") (pin "7") (pinfunction "7_7") (pintype "passive"))
    )
    (net (code "83") (name "unconnected-(X4-Pad8)") (class "Default")
      (node (ref "X4") (pin "8") (pinfunction "8_8") (pintype "passive"))
    )
    (net (code "84") (name "unconnected-(X4-Pad9)") (class "Default")
      (node (ref "X4") (pin "9") (pinfunction "9_9") (pintype "passive"))
    )
    (net (code "85") (name "unconnected-(X4-Pad10)") (class "Default")
      (node (ref "X4") (pin "10") (pinfunction "10_10") (pintype "passive"))
    )
    (net (code "86") (name "unconnected-(X4-Pad11)") (class "Default")
      (node (ref "X4") (pin "11") (pinfunction "11_11") (pintype "passive"))
    )
    (net (code "87") (name "unconnected-(X4-Pad12)") (class "Default")
      (node (ref "X4") (pin "12") (pinfunction "12_12") (pintype "passive"))
    )
    (net (code "88") (name "unconnected-(X4-Pad13)") (class "Default")
      (node (ref "X4") (pin "13") (pinfunction "13_13") (pintype "passive"))
    )
    (net (code "89") (name "unconnected-(X4-Pad14)") (class "Default")
      (node (ref "X4") (pin "14") (pinfunction "14_14") (pintype "passive"))
    )
    (net (code "90") (name "unconnected-(X4-Pad15)") (class "Default")
      (node (ref "X4") (pin "15") (pinfunction "15_15") (pintype "passive"))
    )
    (net (code "91") (name "unconnected-(X4-Pad16)") (class "Default")
      (node (ref "X4") (pin "16") (pinfunction "16_16") (pintype "passive"))
    )
    (net (code "92") (name "unconnected-(X4-Pad17)") (class "Default")
      (node (ref "X4") (pin "17") (pinfunction "17_17") (pintype "passive"))
    )
    (net (code "93") (name "unconnected-(X4-Pad18)") (class "Default")
      (node (ref "X4") (pin "18") (pinfunction "18_18") (pintype "passive"))
    )
    (net (code "94") (name "unconnected-(X4-Pad19)") (class "Default")
      (node (ref "X4") (pin "19") (pinfunction "19_19") (pintype "passive"))
    )
    (net (code "95") (name "unconnected-(X4-Pad20)") (class "Default")
      (node (ref "X4") (pin "20") (pinfunction "20_20") (pintype "passive"))
    )
    (net (code "96") (name "unconnected-(X4-Pad21)") (class "Default")
      (node (ref "X4") (pin "21") (pinfunction "21_21") (pintype "passive"))
    )
    (net (code "97") (name "unconnected-(X4-Pad22)") (class "Default")
      (node (ref "X4") (pin "22") (pinfunction "22_22") (pintype "passive"))
    )
    (net (code "98") (name "unconnected-(X4-Pad23)") (class "Default")
      (node (ref "X4") (pin "23") (pinfunction "23_23") (pintype "passive"))
    )
    (net (code "99") (name "unconnected-(X4-Pad24)") (class "Default")
      (node (ref "X4") (pin "24") (pinfunction "24_24") (pintype "passive"))
    )
    (net (code "100") (name "unconnected-(X4-Pad25)") (class "Default")
      (node (ref "X4") (pin "25") (pinfunction "25_25") (pintype "passive"))
    )
    (net (code "101") (name "unconnected-(X4-Pad26)") (class "Default")
      (node (ref "X4") (pin "26") (pinfunction "26_26") (pintype "passive"))
    )
    (net (code "102") (name "unconnected-(X4-Pad27)") (class "Default")
      (node (ref "X4") (pin "27") (pinfunction "27_27") (pintype "passive"))
    )
    (net (code "103") (name "unconnected-(X4-Pad28)") (class "Default")
      (node (ref "X4") (pin "28") (pinfunction "28_28") (pintype "passive"))
    )
    (net (code "104") (name "unconnected-(X4-Pad29)") (class "Default")
      (node (ref "X4") (pin "29") (pinfunction "29_29") (pintype "passive"))
    )
    (net (code "105") (name "unconnected-(X4-Pad30)") (class "Default")
      (node (ref "X4") (pin "30") (pinfunction "30_30") (pintype "passive"))
    )
    (net (code "106") (name "unconnected-(X4-Pad34)") (class "Default")
      (node (ref "X4") (pin "34") (pinfunction "34_34") (pintype "passive"))
    )
    (net (code "107") (name "unconnected-(XRF-CTS-Pad12)") (class "Default")
      (node (ref "XRF") (pin "12") (pinfunction "CTS_12") (pintype "output"))
    )
    (net (code "108") (name "unconnected-(XRF-P0_1-Pad11)") (class "Default")
      (node (ref "XRF") (pin "11") (pinfunction "P0_1_11") (pintype "bidirectional"))
    )
    (net (code "109") (name "unconnected-(XRF-P0_6-Pad14)") (class "Default")
      (node (ref "XRF") (pin "14") (pinfunction "P0_6_14") (pintype "no_connect"))
    )
    (net (code "110") (name "unconnected-(XRF-P0_7-Pad15)") (class "Default")
      (node (ref "XRF") (pin "15") (pinfunction "P0_7_15") (pintype "bidirectional"))
    )
    (net (code "111") (name "unconnected-(XRF-P2_0-Pad16)") (class "Default")
      (node (ref "XRF") (pin "16") (pinfunction "P2_0_16") (pintype "input"))
    )
    (net (code "112") (name "unconnected-(XRF-P2_1-Pad17)") (class "Default")
      (node (ref "XRF") (pin "17") (pinfunction "P2_1_17") (pintype "input"))
    )
    (net (code "113") (name "unconnected-(XRF-P2_2-Pad18)") (class "Default")
      (node (ref "XRF") (pin "18") (pinfunction "P2_2_18") (pintype "bidirectional"))
    )
    (net (code "114") (name "unconnected-(XRF-RTS-Pad4)") (class "Default")
      (node (ref "XRF") (pin "4") (pinfunction "RTS_4") (pintype "bidirectional"))
    )
  )
)
